# SCH_Final-2_2024-12-22.net
KiCad netlist of a schematic drawn in EasyEDA
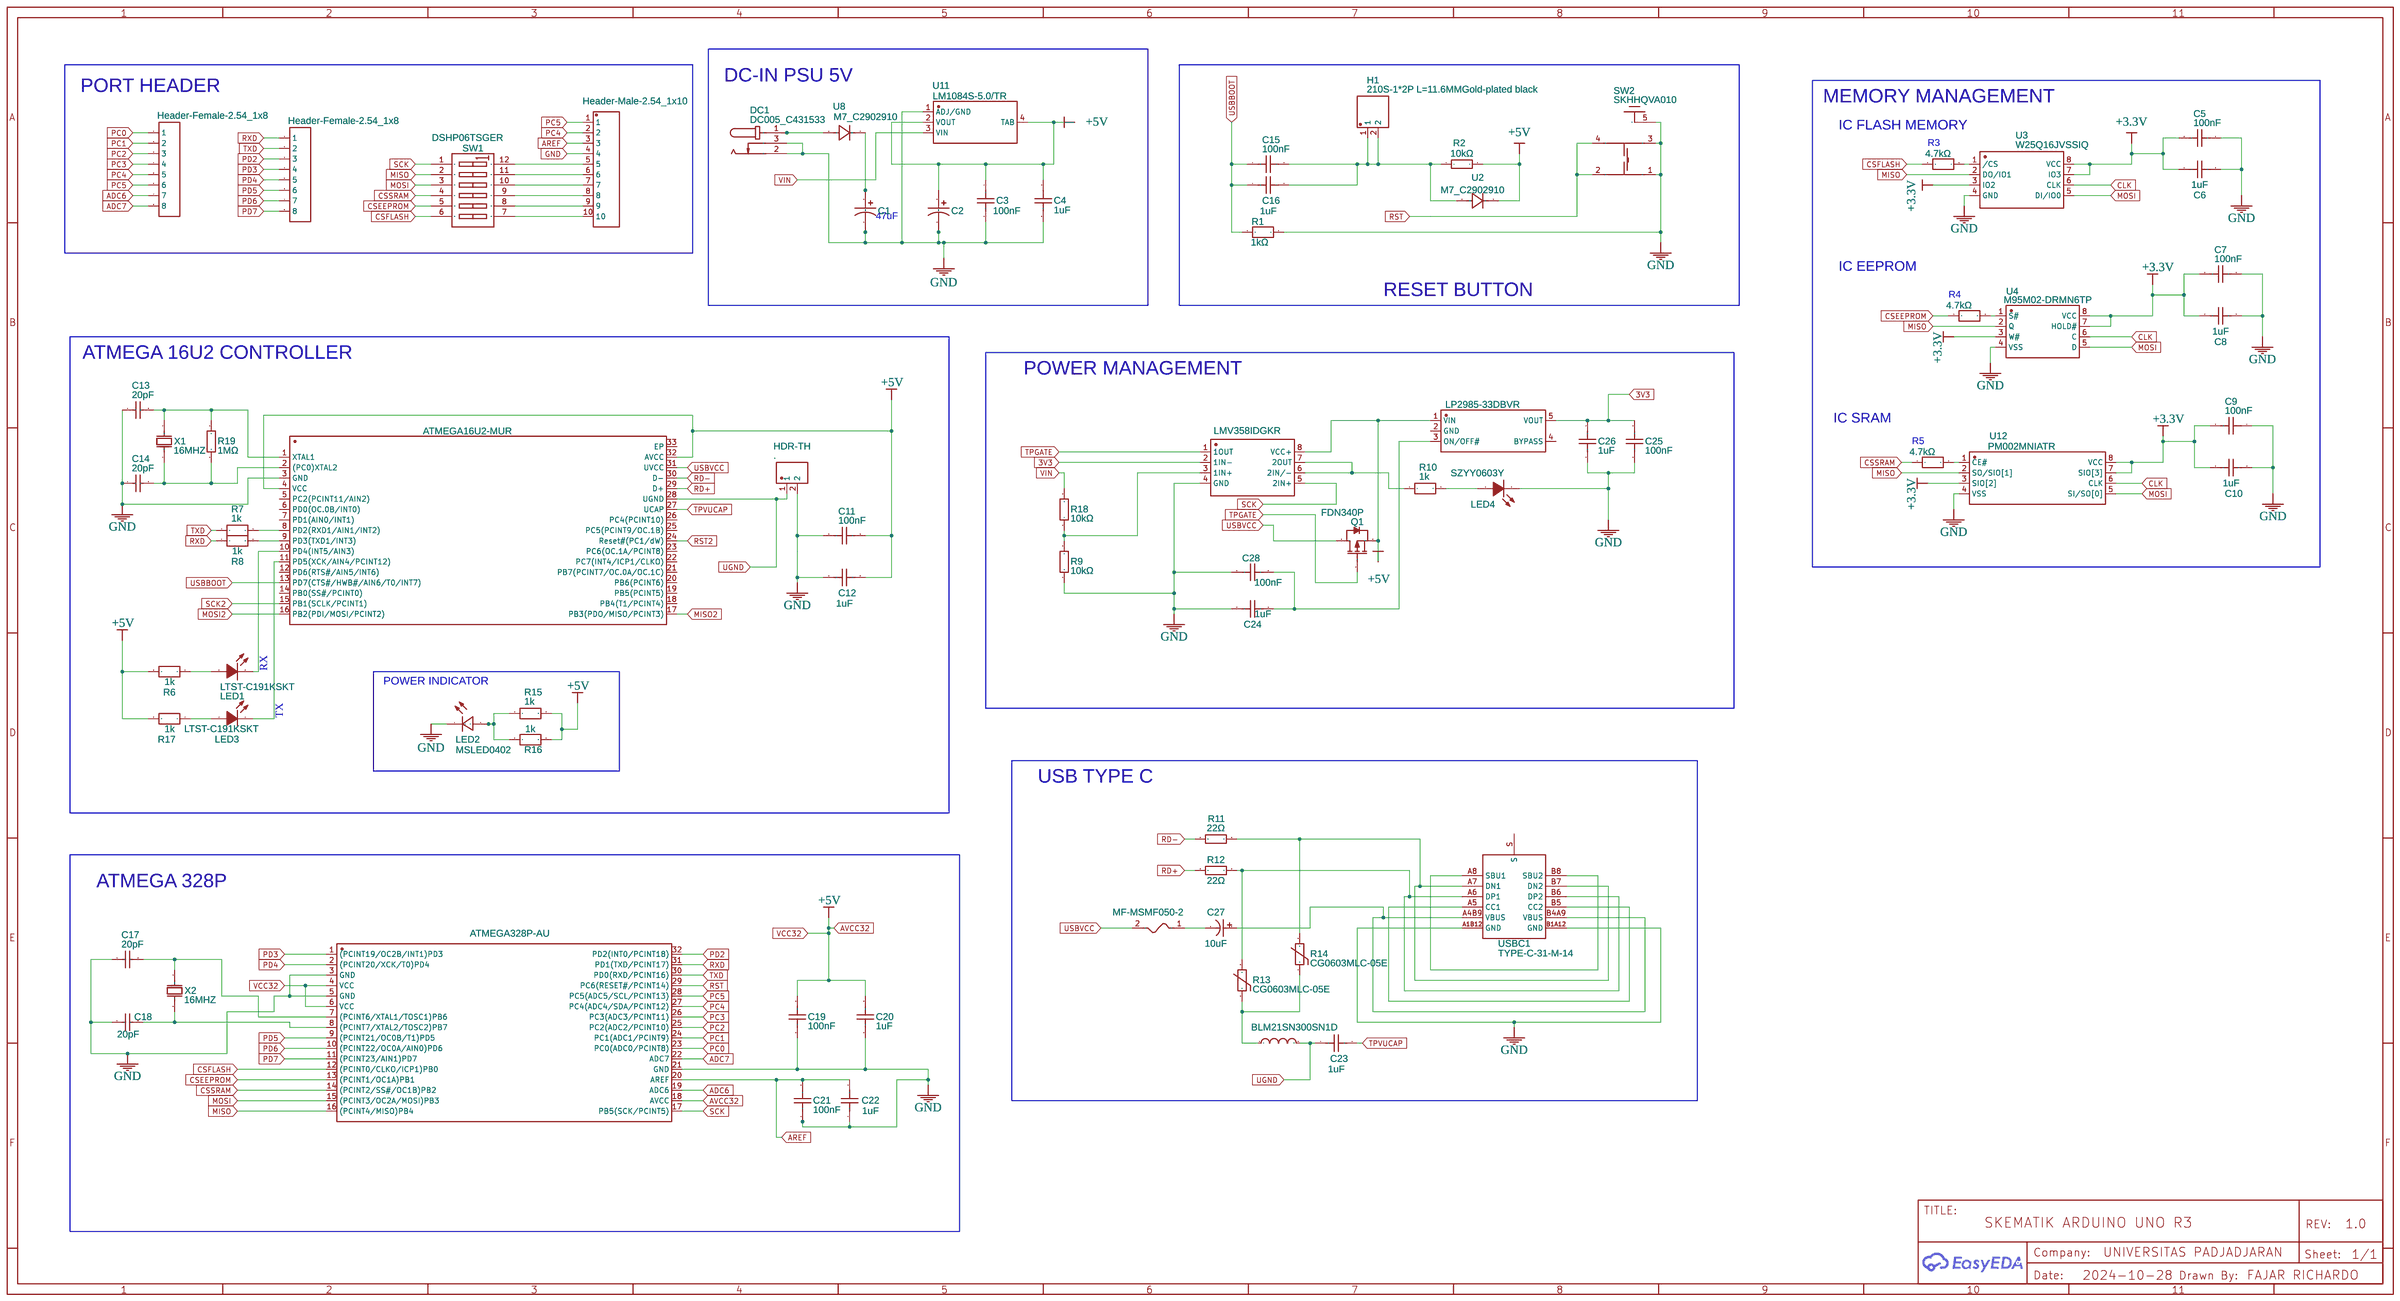
[diagram p0: schematic sheet]

(export (version "E")
  (design (tool "Eeschema 10.0.6"))
  (components
    (comp (ref "C1")
      (value "47uF")
      (fields
        (field (name "Manufacturer Part") "16SEV47M6.3X5.5")
        (field (name "Manufacturer") "rubycon(红宝石)")
      )
      (libsource (lib "") (part "16SEV47M6.3X5.5"))
    )
    (comp (ref "C2")
      (value "47uF")
      (fields
        (field (name "Manufacturer Part") "16SEV47M6.3X5.5")
        (field (name "Manufacturer") "rubycon(红宝石)")
      )
      (libsource (lib "") (part "16SEV47M6.3X5.5"))
    )
    (comp (ref "C3") (value "100nF") (libsource (lib "") (part "C_0402_US_1")))
    (comp (ref "C4") (value "1uF") (libsource (lib "") (part "C_0402_US_1")))
    (comp (ref "C5")
      (value "100nF")
      (fields
        (field (name "Manufacturer Part") "CL02A104KQ2NNNC")
        (field (name "Manufacturer") "SAMSUNG(三星)")
      )
      (libsource (lib "") (part "CL02A104KQ2NNNC"))
    )
    (comp (ref "C6")
      (value "1uF")
      (fields
        (field (name "Manufacturer Part") "1uf/250V/CBBCapacitor")
        (field (name "Manufacturer") "ReliaPro")
      )
      (libsource (lib "") (part "1uf/250V/CBBCapacitor"))
    )
    (comp (ref "C7")
      (value "100nF")
      (fields
        (field (name "Manufacturer Part") "CL02A104KQ2NNNC")
        (field (name "Manufacturer") "SAMSUNG(三星)")
      )
      (libsource (lib "") (part "CL02A104KQ2NNNC"))
    )
    (comp (ref "C8")
      (value "1uF")
      (fields
        (field (name "Manufacturer Part") "1uf/250V/CBBCapacitor")
        (field (name "Manufacturer") "ReliaPro")
      )
      (libsource (lib "") (part "1uf/250V/CBBCapacitor"))
    )
    (comp (ref "C9")
      (value "100nF")
      (fields
        (field (name "Manufacturer Part") "CL02A104KQ2NNNC")
        (field (name "Manufacturer") "SAMSUNG(三星)")
      )
      (libsource (lib "") (part "CL02A104KQ2NNNC"))
    )
    (comp (ref "C10")
      (value "1uF")
      (fields
        (field (name "Manufacturer Part") "1uf/250V/CBBCapacitor")
        (field (name "Manufacturer") "ReliaPro")
      )
      (libsource (lib "") (part "1uf/250V/CBBCapacitor"))
    )
    (comp (ref "C11") (value "100nF") (libsource (lib "") (part "C_0402_US")))
    (comp (ref "C12") (value "1uF") (libsource (lib "") (part "C_0402_US")))
    (comp (ref "C13")
      (value "20pF")
      (fields
        (field (name "Manufacturer Part") "GRM1885C1H200JA01D")
        (field (name "Manufacturer") "muRata(村田)")
      )
      (libsource (lib "") (part "GRM1885C1H200JA01D"))
    )
    (comp (ref "C14")
      (value "20pF")
      (fields
        (field (name "Manufacturer Part") "GRM1885C1H200JA01D")
        (field (name "Manufacturer") "muRata(村田)")
      )
      (libsource (lib "") (part "GRM1885C1H200JA01D"))
    )
    (comp (ref "C15") (value "100nF") (libsource (lib "") (part "C_0402_US")))
    (comp (ref "C16") (value "1uF") (libsource (lib "") (part "C_0402_US")))
    (comp (ref "C17")
      (value "20pF")
      (fields
        (field (name "Manufacturer Part") "GRM1885C1H200JA01D")
        (field (name "Manufacturer") "muRata(村田)")
      )
      (libsource (lib "") (part "GRM1885C1H200JA01D"))
    )
    (comp (ref "C18")
      (value "20pF")
      (fields
        (field (name "Manufacturer Part") "GRM1885C1H200JA01D")
        (field (name "Manufacturer") "muRata(村田)")
      )
      (libsource (lib "") (part "GRM1885C1H200JA01D"))
    )
    (comp (ref "C19") (value "100nF") (libsource (lib "") (part "C_0402_US_2")))
    (comp (ref "C20") (value "1uF") (libsource (lib "") (part "C_0402_US_2")))
    (comp (ref "C21") (value "100nF") (libsource (lib "") (part "C_0402_US_2")))
    (comp (ref "C22") (value "1uF") (libsource (lib "") (part "C_0402_US_2")))
    (comp (ref "C23") (value "1uF") (libsource (lib "") (part "C_0402_US")))
    (comp (ref "C24") (value "1uF") (libsource (lib "") (part "C_0402_US")))
    (comp (ref "C25") (value "100nF") (libsource (lib "") (part "C_0402_US_1")))
    (comp (ref "C26") (value "1uF") (libsource (lib "") (part "C_0402_US_1")))
    (comp (ref "C27")
      (value "10uF")
      (fields
        (field (name "Manufacturer Part") "KS106M050C07RR0VH2FP0")
        (field (name "Manufacturer") "CX(承兴)")
      )
      (libsource (lib "") (part "electrolytic capacitor10UF50V"))
    )
    (comp (ref "C28") (value "100nF") (libsource (lib "") (part "C_0402_US")))
    (comp (ref "DC1")
      (value "DC005_C431533")
      (fields (field (name "Manufacturer Part") "DC005") (field (name "Manufacturer") "SHOU HAN(首韩)"))
      (libsource (lib "") (part "DC005_C431533"))
    )
    (comp (ref "H1")
      (value "210S-1*2P L=11.6MMGold-plated black")
      (fields (field (name "Manufacturer Part") "B-2100S02P-A110") (field (name "Manufacturer") "Ckmtw(灿科盟)"))
      (libsource (lib "") (part "210S-1*2P L=11.6MMGold-plated black"))
    )
    (comp (ref "HDR-TH")
      (value ".")
      (fields (field (name "Manufacturer Part") "22-28-4020") (field (name "Manufacturer") "MOLEX"))
      (libsource (lib "") (part "22-28-4020"))
    )
    (comp (ref "LED1")
      (value "LTST-C191KSKT")
      (fields (field (name "Manufacturer") "LITEON(光宝)"))
      (libsource (lib "") (part "LTST-C191KSKT"))
    )
    (comp (ref "LED2") (value "MSLED0402") (libsource (lib "") (part "MSLED0402")))
    (comp (ref "LED3")
      (value "LTST-C191KSKT")
      (fields (field (name "Manufacturer") "LITEON(光宝)"))
      (libsource (lib "") (part "LTST-C191KSKT"))
    )
    (comp (ref "LED4")
      (value "SZYY0603Y")
      (fields (field (name "Manufacturer") "yongyu(永裕光电)"))
      (libsource (lib "") (part "SZYY0603Y"))
    )
    (comp (ref "PBX")
      (value "Header-Male-2.54_1x10")
      (fields (field (name "Manufacturer Part") "2.54-1*10P针") (field (name "Manufacturer") "BOOMELE(博穆精密)"))
      (libsource (lib "") (part "Header-Male-2.54_1x10"))
    )
    (comp (ref "PCX")
      (value "Header-Female-2.54_1x8")
      (fields (field (name "Manufacturer Part") "2.54-1*8P母环保") (field (name "Manufacturer") "BOOMELE(博穆精密)"))
      (libsource (lib "") (part "Header-Female-2.54_1x8_1"))
    )
    (comp (ref "PDX")
      (value "Header-Female-2.54_1x8")
      (fields (field (name "Manufacturer Part") "2.54-1*8P母环保") (field (name "Manufacturer") "BOOMELE(博穆精密)"))
      (libsource (lib "") (part "Header-Female-2.54_1x8"))
    )
    (comp (ref "Q1")
      (value "FDN340P")
      (fields (field (name "Manufacturer") "onsemi(安森美)"))
      (libsource (lib "") (part "FDN340P"))
    )
    (comp (ref "R1") (value "1kΩ") (libsource (lib "") (part "R_0402_EU")))
    (comp (ref "R2")
      (value "10kΩ")
      (fields (field (name "Manufacturer Part") "RC0603FR-0710KL") (field (name "Manufacturer") "YAGEO(国巨)"))
      (libsource (lib "") (part "RC0603FR-0710KL"))
    )
    (comp (ref "R6") (value "1k") (libsource (lib "") (part "R_0402_EU")))
    (comp (ref "R7") (value "1k") (libsource (lib "") (part "R_0402_EU_1")))
    (comp (ref "R8") (value "1k") (libsource (lib "") (part "R_0402_EU_1")))
    (comp (ref "R9")
      (value "10kΩ")
      (fields (field (name "Manufacturer Part") "RC0603FR-0710KL") (field (name "Manufacturer") "YAGEO(国巨)"))
      (libsource (lib "") (part "RC0603FR-0710KL_1"))
    )
    (comp (ref "R10") (value "1k") (libsource (lib "") (part "R_0402_EU_1")))
    (comp (ref "R11")
      (value "22Ω")
      (fields (field (name "Manufacturer Part") "RC0805FR-0722RL") (field (name "Manufacturer") "YAGEO(国巨)"))
      (libsource (lib "") (part "RC0805FR-0722RL"))
    )
    (comp (ref "R12")
      (value "22Ω")
      (fields (field (name "Manufacturer Part") "RC0805FR-0722RL") (field (name "Manufacturer") "YAGEO(国巨)"))
      (libsource (lib "") (part "RC0805FR-0722RL"))
    )
    (comp (ref "R13")
      (value "CG0603MLC-05E")
      (fields (field (name "Manufacturer") "BOURNS"))
      (libsource (lib "") (part "CG0603MLC-05E"))
    )
    (comp (ref "R14")
      (value "CG0603MLC-05E")
      (fields (field (name "Manufacturer") "BOURNS"))
      (libsource (lib "") (part "CG0603MLC-05E"))
    )
    (comp (ref "R15") (value "1k") (libsource (lib "") (part "R_0402_EU_1")))
    (comp (ref "R16") (value "1k") (libsource (lib "") (part "R_0402_EU_1")))
    (comp (ref "R17") (value "1k") (libsource (lib "") (part "R_0402_EU")))
    (comp (ref "R18")
      (value "10kΩ")
      (fields (field (name "Manufacturer Part") "RC0603FR-0710KL") (field (name "Manufacturer") "YAGEO(国巨)"))
      (libsource (lib "") (part "RC0603FR-0710KL_1"))
    )
    (comp (ref "R19")
      (value "1MΩ")
      (fields (field (name "Manufacturer Part") "RC0603FR-071ML") (field (name "Manufacturer") "YAGEO(国巨)"))
      (libsource (lib "") (part "RC0603FR-071ML"))
    )
    (comp (ref "SW1")
      (value "DSHP06TSGER")
      (fields (field (name "Manufacturer Part") "DSHP06TSGET") (field (name "Manufacturer") "YE"))
      (libsource (lib "") (part "DSHP06TSGER"))
    )
    (comp (ref "SW2")
      (value "SKHHQVA010")
      (fields (field (name "Manufacturer") "ALPSALPINE(阿尔卑斯阿尔派)"))
      (libsource (lib "") (part "SKHHQVA010"))
    )
    (comp (ref "U1")
      (value "ATMEGA16U2-MUR")
      (fields (field (name "Manufacturer") "MICROCHIP(美国微芯)"))
      (libsource (lib "") (part "ATMEGA16U2-MUR"))
    )
    (comp (ref "U2")
      (value "M7_C2902910")
      (fields (field (name "Manufacturer Part") "M7") (field (name "Manufacturer") "MSKSEMI(美森科)"))
      (libsource (lib "") (part "M7_C2902910"))
    )
    (comp (ref "U3")
      (value "W25Q16JVSSIQ")
      (fields (field (name "Manufacturer") "WINBOND(华邦)"))
      (libsource (lib "") (part "W25Q16JVSSIQ"))
    )
    (comp (ref "U4")
      (value "M95M02-DRMN6TP")
      (fields (field (name "Manufacturer") "ST(意法半导体)"))
      (libsource (lib "") (part "M95M02-DRMN6TP"))
    )
    (comp (ref "U5")
      (value "ATMEGA328P-AU")
      (fields (field (name "Manufacturer") "MICROCHIP(美国微芯)"))
      (libsource (lib "") (part "ATMEGA328P-AU"))
    )
    (comp (ref "U6")
      (value "BLM21SN300SN1D")
      (fields (field (name "Manufacturer") "muRata(村田)"))
      (libsource (lib "") (part "BLM21SN300SN1D"))
    )
    (comp (ref "U7")
      (value "MF-MSMF050-2")
      (fields (field (name "Manufacturer") "BOURNS"))
      (libsource (lib "") (part "MF-MSMF050-2"))
    )
    (comp (ref "U8")
      (value "M7_C2902910")
      (fields (field (name "Manufacturer Part") "M7") (field (name "Manufacturer") "MSKSEMI(美森科)"))
      (libsource (lib "") (part "M7_C2902910"))
    )
    (comp (ref "U9")
      (value "LP2985-33DBVR")
      (fields (field (name "Manufacturer") "TI(德州仪器)"))
      (libsource (lib "") (part "LP2985-33DBVR"))
    )
    (comp (ref "U10")
      (value "LMV358IDGKR")
      (fields (field (name "Manufacturer") "TI(德州仪器)"))
      (libsource (lib "") (part "LMV358IDGKR"))
    )
    (comp (ref "U11")
      (value "LM1084S-5.0/TR")
      (fields (field (name "Manufacturer") "HGSEMI(华冠)"))
      (libsource (lib "") (part "LM1084S-5.0/TR"))
    )
    (comp (ref "U12")
      (value "PM002MNIATR")
      (fields (field (name "Manufacturer") "Siproin(上海矽朋)"))
      (libsource (lib "") (part "PM002MNIATR"))
    )
    (comp (ref "U17")
      (value "4.7kΩ")
      (fields (field (name "Manufacturer Part") "0805 ±1% 4K7") (field (name "Manufacturer") "VO(翔胜)"))
      (libsource (lib "") (part "0805 ±1% 4K7"))
    )
    (comp (ref "U18")
      (value "4.7kΩ")
      (fields (field (name "Manufacturer Part") "0805 ±1% 4K7") (field (name "Manufacturer") "VO(翔胜)"))
      (libsource (lib "") (part "0805 ±1% 4K7"))
    )
    (comp (ref "U19")
      (value "4.7kΩ")
      (fields (field (name "Manufacturer Part") "0805 ±1% 4K7") (field (name "Manufacturer") "VO(翔胜)"))
      (libsource (lib "") (part "0805 ±1% 4K7"))
    )
    (comp (ref "USBC1")
      (value "TYPE-C-31-M-14")
      (fields (field (name "Manufacturer") "韩国韩荣"))
      (libsource (lib "") (part "TYPE-C-31-M-14"))
    )
    (comp (ref "X1")
      (value "16MHZ")
      (fields (field (name "Manufacturer Part") "X503216MSD2GC") (field (name "Manufacturer") "YXC"))
      (libsource (lib "") (part "X503216MSD2GC"))
    )
    (comp (ref "X2")
      (value "16MHZ")
      (fields (field (name "Manufacturer Part") "X503216MSD2GC") (field (name "Manufacturer") "YXC"))
      (libsource (lib "") (part "X503216MSD2GC"))
    )
  )
  (nets
    (net (code "1") (name "+3.3V") (class "Default")
      (node (ref "C10") (pin "1") (pinfunction "1_1") (pintype "unspecified"))
      (node (ref "C5") (pin "2") (pinfunction "2_2") (pintype "unspecified"))
      (node (ref "C6") (pin "1") (pinfunction "1_1") (pintype "unspecified"))
      (node (ref "C7") (pin "2") (pinfunction "2_2") (pintype "unspecified"))
      (node (ref "C8") (pin "1") (pinfunction "1_1") (pintype "unspecified"))
      (node (ref "C9") (pin "2") (pinfunction "2_2") (pintype "unspecified"))
      (node (ref "U12") (pin "3") (pinfunction "SIO[2]_3") (pintype "unspecified"))
      (node (ref "U12") (pin "7") (pinfunction "SIO[3]_7") (pintype "unspecified"))
      (node (ref "U12") (pin "8") (pinfunction "VCC_8") (pintype "unspecified"))
      (node (ref "U3") (pin "3") (pinfunction "IO2_3") (pintype "unspecified"))
      (node (ref "U3") (pin "7") (pinfunction "IO3_7") (pintype "unspecified"))
      (node (ref "U3") (pin "8") (pinfunction "VCC_8") (pintype "unspecified"))
      (node (ref "U4") (pin "3") (pinfunction "W#_3") (pintype "unspecified"))
      (node (ref "U4") (pin "7") (pinfunction "HOLD#_7") (pintype "unspecified"))
      (node (ref "U4") (pin "8") (pinfunction "VCC_8") (pintype "unspecified"))
    )
    (net (code "2") (name "3V3") (class "Default")
      (node (ref "C25") (pin "1") (pinfunction "1_1") (pintype "unspecified"))
      (node (ref "C26") (pin "1") (pinfunction "1_1") (pintype "unspecified"))
      (node (ref "U10") (pin "2") (pinfunction "1IN-_2") (pintype "unspecified"))
      (node (ref "U9") (pin "5") (pinfunction "VOUT_5") (pintype "unspecified"))
    )
    (net (code "3") (name "ADC6") (class "Default")
      (node (ref "PDX") (pin "7") (pinfunction "7_7") (pintype "input"))
      (node (ref "U5") (pin "19") (pinfunction "ADC6_19") (pintype "unspecified"))
    )
    (net (code "4") (name "ADC7") (class "Default")
      (node (ref "PDX") (pin "8") (pinfunction "8_8") (pintype "input"))
      (node (ref "U5") (pin "22") (pinfunction "ADC7_22") (pintype "unspecified"))
    )
    (net (code "5") (name "AREF") (class "Default")
      (node (ref "C21") (pin "2") (pinfunction "2_2") (pintype "unspecified"))
      (node (ref "C22") (pin "2") (pinfunction "2_2") (pintype "unspecified"))
      (node (ref "PBX") (pin "3") (pinfunction "3_3") (pintype "unspecified"))
      (node (ref "U5") (pin "20") (pinfunction "AREF_20") (pintype "unspecified"))
    )
    (net (code "6") (name "AVCC32") (class "Default")
      (node (ref "C11") (pin "2") (pinfunction "2_2") (pintype "unspecified"))
      (node (ref "C12") (pin "2") (pinfunction "2_2") (pintype "unspecified"))
      (node (ref "C19") (pin "2") (pinfunction "2_2") (pintype "unspecified"))
      (node (ref "C2") (pin "1") (pinfunction "1_1") (pintype "unspecified"))
      (node (ref "C20") (pin "2") (pinfunction "2_2") (pintype "unspecified"))
      (node (ref "C3") (pin "1") (pinfunction "1_1") (pintype "unspecified"))
      (node (ref "C4") (pin "1") (pinfunction "1_1") (pintype "unspecified"))
      (node (ref "Q1") (pin "2") (pinfunction "S_2") (pintype "unspecified"))
      (node (ref "R15") (pin "2") (pinfunction "2_2") (pintype "unspecified"))
      (node (ref "R16") (pin "2") (pinfunction "2_2") (pintype "unspecified"))
      (node (ref "R17") (pin "2") (pinfunction "2_2") (pintype "unspecified"))
      (node (ref "R2") (pin "2") (pinfunction "2_2") (pintype "input"))
      (node (ref "R6") (pin "2") (pinfunction "2_2") (pintype "unspecified"))
      (node (ref "U1") (pin "32") (pinfunction "AVCC_32") (pintype "unspecified"))
      (node (ref "U1") (pin "4") (pinfunction "VCC_4") (pintype "unspecified"))
      (node (ref "U10") (pin "8") (pinfunction "VCC+_8") (pintype "unspecified"))
      (node (ref "U11") (pin "2") (pinfunction "VOUT_2") (pintype "unspecified"))
      (node (ref "U11") (pin "4") (pinfunction "TAB_4") (pintype "unspecified"))
      (node (ref "U2") (pin "1") (pinfunction "Cathode_1") (pintype "unspecified"))
      (node (ref "U5") (pin "18") (pinfunction "AVCC_18") (pintype "unspecified"))
      (node (ref "U5") (pin "4") (pinfunction "VCC_4") (pintype "unspecified"))
      (node (ref "U5") (pin "6") (pinfunction "VCC_6") (pintype "unspecified"))
      (node (ref "U9") (pin "1") (pinfunction "VIN_1") (pintype "unspecified"))
    )
    (net (code "7") (name "CLK") (class "Default")
      (node (ref "U12") (pin "6") (pinfunction "CLK_6") (pintype "unspecified"))
      (node (ref "U3") (pin "6") (pinfunction "CLK_6") (pintype "unspecified"))
      (node (ref "U4") (pin "6") (pinfunction "C_6") (pintype "unspecified"))
    )
    (net (code "8") (name "CSEEPROM") (class "Default")
      (node (ref "SW1") (pin "5") (pinfunction "A5_5") (pintype "input"))
      (node (ref "U18") (pin "1") (pinfunction "1_1") (pintype "unspecified"))
      (node (ref "U5") (pin "13") (pinfunction "(PCINT1/OC1A)PB1_13") (pintype "unspecified"))
    )
    (net (code "9") (name "CSFLASH") (class "Default")
      (node (ref "SW1") (pin "6") (pinfunction "A6_6") (pintype "input"))
      (node (ref "U17") (pin "1") (pinfunction "1_1") (pintype "unspecified"))
      (node (ref "U5") (pin "12") (pinfunction "(PCINT0/CLKO/ICP1)PB0_12") (pintype "unspecified"))
    )
    (net (code "10") (name "CSSRAM") (class "Default")
      (node (ref "SW1") (pin "4") (pinfunction "A4_4") (pintype "input"))
      (node (ref "U19") (pin "1") (pinfunction "1_1") (pintype "unspecified"))
      (node (ref "U5") (pin "14") (pinfunction "(PCINT2/SS#/OC1B)PB2_14") (pintype "unspecified"))
    )
    (net (code "11") (name "GND") (class "Default")
      (node (ref "C1") (pin "2") (pinfunction "2_2") (pintype "unspecified"))
      (node (ref "C10") (pin "2") (pinfunction "2_2") (pintype "unspecified"))
      (node (ref "C11") (pin "1") (pinfunction "1_1") (pintype "unspecified"))
      (node (ref "C12") (pin "1") (pinfunction "1_1") (pintype "unspecified"))
      (node (ref "C13") (pin "1") (pinfunction "1_1") (pintype "input"))
      (node (ref "C14") (pin "1") (pinfunction "1_1") (pintype "input"))
      (node (ref "C17") (pin "1") (pinfunction "1_1") (pintype "input"))
      (node (ref "C18") (pin "1") (pinfunction "1_1") (pintype "input"))
      (node (ref "C19") (pin "1") (pinfunction "1_1") (pintype "unspecified"))
      (node (ref "C2") (pin "2") (pinfunction "2_2") (pintype "unspecified"))
      (node (ref "C20") (pin "1") (pinfunction "1_1") (pintype "unspecified"))
      (node (ref "C21") (pin "1") (pinfunction "1_1") (pintype "unspecified"))
      (node (ref "C22") (pin "1") (pinfunction "1_1") (pintype "unspecified"))
      (node (ref "C24") (pin "1") (pinfunction "1_1") (pintype "unspecified"))
      (node (ref "C25") (pin "2") (pinfunction "2_2") (pintype "unspecified"))
      (node (ref "C26") (pin "2") (pinfunction "2_2") (pintype "unspecified"))
      (node (ref "C28") (pin "1") (pinfunction "1_1") (pintype "unspecified"))
      (node (ref "C3") (pin "2") (pinfunction "2_2") (pintype "unspecified"))
      (node (ref "C4") (pin "2") (pinfunction "2_2") (pintype "unspecified"))
      (node (ref "C5") (pin "1") (pinfunction "1_1") (pintype "unspecified"))
      (node (ref "C6") (pin "2") (pinfunction "2_2") (pintype "unspecified"))
      (node (ref "C7") (pin "1") (pinfunction "1_1") (pintype "unspecified"))
      (node (ref "C8") (pin "2") (pinfunction "2_2") (pintype "unspecified"))
      (node (ref "C9") (pin "1") (pinfunction "1_1") (pintype "unspecified"))
      (node (ref "DC1") (pin "2") (pinfunction "2_2") (pintype "unspecified"))
      (node (ref "DC1") (pin "3") (pinfunction "3_3") (pintype "unspecified"))
      (node (ref "HDR-TH") (pin "2") (pinfunction "2_2") (pintype "unspecified"))
      (node (ref "LED2") (pin "1") (pinfunction "C_1") (pintype "unspecified"))
      (node (ref "LED4") (pin "2") (pinfunction "-_2") (pintype "unspecified"))
      (node (ref "PBX") (pin "4") (pinfunction "4_4") (pintype "unspecified"))
      (node (ref "R1") (pin "1") (pinfunction "1_1") (pintype "unspecified"))
      (node (ref "R9") (pin "1") (pinfunction "1_1") (pintype "input"))
      (node (ref "SW2") (pin "1") (pinfunction "1_1") (pintype "unspecified"))
      (node (ref "SW2") (pin "3") (pinfunction "3_3") (pintype "unspecified"))
      (node (ref "SW2") (pin "5") (pinfunction "5_5") (pintype "unspecified"))
      (node (ref "U1") (pin "3") (pinfunction "GND_3") (pintype "unspecified"))
      (node (ref "U10") (pin "4") (pinfunction "GND_4") (pintype "unspecified"))
      (node (ref "U11") (pin "1") (pinfunction "ADJ/GND_1") (pintype "unspecified"))
      (node (ref "U12") (pin "4") (pinfunction "VSS_4") (pintype "unspecified"))
      (node (ref "U3") (pin "4") (pinfunction "GND_4") (pintype "unspecified"))
      (node (ref "U4") (pin "4") (pinfunction "VSS_4") (pintype "unspecified"))
      (node (ref "U5") (pin "21") (pinfunction "GND_21") (pintype "unspecified"))
      (node (ref "U5") (pin "3") (pinfunction "GND_3") (pintype "unspecified"))
      (node (ref "U5") (pin "5") (pinfunction "GND_5") (pintype "unspecified"))
      (node (ref "USBC1") (pin "A1B12") (pinfunction "GND_A1B12") (pintype "unspecified"))
      (node (ref "USBC1") (pin "B1A12") (pinfunction "GND_B1A12") (pintype "unspecified"))
    )
    (net (code "12") (name "MISO") (class "Default")
      (node (ref "SW1") (pin "2") (pinfunction "A2_2") (pintype "input"))
      (node (ref "U12") (pin "2") (pinfunction "SO/SIO[1]_2") (pintype "unspecified"))
      (node (ref "U3") (pin "2") (pinfunction "DO/IO1_2") (pintype "unspecified"))
      (node (ref "U4") (pin "2") (pinfunction "Q_2") (pintype "unspecified"))
      (node (ref "U5") (pin "16") (pinfunction "(PCINT4/MISO)PB4_16") (pintype "unspecified"))
    )
    (net (code "13") (name "MISO2") (class "Default")
      (node (ref "U1") (pin "17") (pinfunction "PB3(PDO/MISO/PCINT3)_17") (pintype "unspecified"))
    )
    (net (code "14") (name "MOSI") (class "Default")
      (node (ref "SW1") (pin "3") (pinfunction "A3_3") (pintype "input"))
      (node (ref "U12") (pin "5") (pinfunction "SI/SO[0]_5") (pintype "unspecified"))
      (node (ref "U3") (pin "5") (pinfunction "DI/IO0_5") (pintype "unspecified"))
      (node (ref "U4") (pin "5") (pinfunction "D_5") (pintype "unspecified"))
      (node (ref "U5") (pin "15") (pinfunction "(PCINT3/OC2A/MOSI)PB3_15") (pintype "unspecified"))
    )
    (net (code "15") (name "MOSI2") (class "Default")
      (node (ref "U1") (pin "16") (pinfunction "PB2(PDI/MOSI/PCINT2)_16") (pintype "unspecified"))
    )
    (net (code "16") (name "Net-(C27-+)") (class "Default")
      (node (ref "C27") (pin "1") (pinfunction "+_1") (pintype "input"))
      (node (ref "USBC1") (pin "A4B9") (pinfunction "VBUS_A4B9") (pintype "unspecified"))
      (node (ref "USBC1") (pin "B4A9") (pinfunction "VBUS_B4A9") (pintype "unspecified"))
    )
    (net (code "17") (name "Net-(C27--)") (class "Default")
      (node (ref "C27") (pin "2") (pinfunction "-_2") (pintype "input"))
      (node (ref "U7") (pin "1") (pinfunction "1_1") (pintype "unspecified"))
    )
    (net (code "18") (name "Net-(LED1-+)") (class "Default")
      (node (ref "LED1") (pin "2") (pinfunction "+_2") (pintype "unspecified"))
      (node (ref "R6") (pin "1") (pinfunction "1_1") (pintype "unspecified"))
    )
    (net (code "19") (name "Net-(LED1--)") (class "Default")
      (node (ref "LED1") (pin "1") (pinfunction "-_1") (pintype "unspecified"))
      (node (ref "U1") (pin "10") (pinfunction "PD4(INT5/AIN3)_10") (pintype "unspecified"))
    )
    (net (code "20") (name "Net-(LED2-A)") (class "Default")
      (node (ref "LED2") (pin "2") (pinfunction "A_2") (pintype "unspecified"))
      (node (ref "R15") (pin "1") (pinfunction "1_1") (pintype "unspecified"))
      (node (ref "R16") (pin "1") (pinfunction "1_1") (pintype "unspecified"))
    )
    (net (code "21") (name "Net-(LED3-+)") (class "Default")
      (node (ref "LED3") (pin "2") (pinfunction "+_2") (pintype "unspecified"))
      (node (ref "R17") (pin "1") (pinfunction "1_1") (pintype "unspecified"))
    )
    (net (code "22") (name "Net-(LED3--)") (class "Default")
      (node (ref "LED3") (pin "1") (pinfunction "-_1") (pintype "unspecified"))
      (node (ref "U1") (pin "11") (pinfunction "PD5(XCK/AIN4/PCINT12)_11") (pintype "unspecified"))
    )
    (net (code "23") (name "Net-(LED4-+)") (class "Default")
      (node (ref "LED4") (pin "1") (pinfunction "+_1") (pintype "unspecified"))
      (node (ref "R10") (pin "2") (pinfunction "2_2") (pintype "unspecified"))
    )
    (net (code "24") (name "Net-(R13-Pad1)") (class "Default")
      (node (ref "R13") (pin "1") (pinfunction "1_1") (pintype "unspecified"))
      (node (ref "R14") (pin "1") (pinfunction "1_1") (pintype "unspecified"))
      (node (ref "U6") (pin "1") (pinfunction "1_1") (pintype "unspecified"))
    )
    (net (code "25") (name "Net-(SW1-B1)") (class "Default")
      (node (ref "PBX") (pin "5") (pinfunction "5_5") (pintype "unspecified"))
      (node (ref "SW1") (pin "12") (pinfunction "B1_12") (pintype "input"))
    )
    (net (code "26") (name "Net-(SW1-B2)") (class "Default")
      (node (ref "PBX") (pin "6") (pinfunction "6_6") (pintype "unspecified"))
      (node (ref "SW1") (pin "11") (pinfunction "B2_11") (pintype "input"))
    )
    (net (code "27") (name "Net-(SW1-B3)") (class "Default")
      (node (ref "PBX") (pin "7") (pinfunction "7_7") (pintype "unspecified"))
      (node (ref "SW1") (pin "10") (pinfunction "B3_10") (pintype "input"))
    )
    (net (code "28") (name "Net-(SW1-B4)") (class "Default")
      (node (ref "PBX") (pin "8") (pinfunction "8_8") (pintype "unspecified"))
      (node (ref "SW1") (pin "9") (pinfunction "B4_9") (pintype "input"))
    )
    (net (code "29") (name "Net-(SW1-B5)") (class "Default")
      (node (ref "PBX") (pin "9") (pinfunction "9_9") (pintype "unspecified"))
      (node (ref "SW1") (pin "8") (pinfunction "B5_8") (pintype "input"))
    )
    (net (code "30") (name "Net-(SW1-B6)") (class "Default")
      (node (ref "PBX") (pin "10") (pinfunction "10_10") (pintype "unspecified"))
      (node (ref "SW1") (pin "7") (pinfunction "B6_7") (pintype "input"))
    )
    (net (code "31") (name "Net-(U1-(PC0)XTAL2)") (class "Default")
      (node (ref "C14") (pin "2") (pinfunction "2_2") (pintype "input"))
      (node (ref "R19") (pin "2") (pinfunction "2_2") (pintype "input"))
      (node (ref "U1") (pin "2") (pinfunction "(PC0)XTAL2_2") (pintype "unspecified"))
      (node (ref "X1") (pin "2") (pinfunction "OSC2_2") (pintype "input"))
    )
    (net (code "32") (name "Net-(U1-PD2(RXD1{slash}AIN1{slash}INT2))") (class "Default")
      (node (ref "R7") (pin "2") (pinfunction "2_2") (pintype "unspecified"))
      (node (ref "U1") (pin "8") (pinfunction "PD2(RXD1/AIN1/INT2)_8") (pintype "unspecified"))
    )
    (net (code "33") (name "Net-(U1-PD3(TXD1{slash}INT3))") (class "Default")
      (node (ref "R8") (pin "2") (pinfunction "2_2") (pintype "unspecified"))
      (node (ref "U1") (pin "9") (pinfunction "PD3(TXD1/INT3)_9") (pintype "unspecified"))
    )
    (net (code "34") (name "Net-(U1-XTAL1)") (class "Default")
      (node (ref "C13") (pin "2") (pinfunction "2_2") (pintype "input"))
      (node (ref "R19") (pin "1") (pinfunction "1_1") (pintype "input"))
      (node (ref "U1") (pin "1") (pinfunction "XTAL1_1") (pintype "unspecified"))
      (node (ref "X1") (pin "1") (pinfunction "OSC1_1") (pintype "input"))
    )
    (net (code "35") (name "Net-(U2-Anode)") (class "Default")
      (node (ref "C15") (pin "2") (pinfunction "2_2") (pintype "unspecified"))
      (node (ref "C16") (pin "2") (pinfunction "2_2") (pintype "unspecified"))
      (node (ref "H1") (pin "1") (pinfunction "1_1") (pintype "unspecified"))
      (node (ref "H1") (pin "2") (pinfunction "2_2") (pintype "unspecified"))
      (node (ref "R2") (pin "1") (pinfunction "1_1") (pintype "input"))
      (node (ref "U2") (pin "2") (pinfunction "Anode_2") (pintype "unspecified"))
    )
    (net (code "36") (name "Net-(U3-{slash}CS)") (class "Default")
      (node (ref "U17") (pin "2") (pinfunction "2_2") (pintype "unspecified"))
      (node (ref "U3") (pin "1") (pinfunction "/CS_1") (pintype "unspecified"))
    )
    (net (code "37") (name "Net-(U4-S#)") (class "Default")
      (node (ref "U18") (pin "2") (pinfunction "2_2") (pintype "unspecified"))
      (node (ref "U4") (pin "1") (pinfunction "S#_1") (pintype "unspecified"))
    )
    (net (code "38") (name "Net-(U5-(PCINT6{slash}XTAL1{slash}TOSC1)PB6)") (class "Default")
      (node (ref "C17") (pin "2") (pinfunction "2_2") (pintype "input"))
      (node (ref "U5") (pin "7") (pinfunction "(PCINT6/XTAL1/TOSC1)PB6_7") (pintype "unspecified"))
      (node (ref "X2") (pin "1") (pinfunction "OSC1_1") (pintype "input"))
    )
    (net (code "39") (name "Net-(U5-(PCINT7{slash}XTAL2{slash}TOSC2)PB7)") (class "Default")
      (node (ref "C18") (pin "2") (pinfunction "2_2") (pintype "input"))
      (node (ref "U5") (pin "8") (pinfunction "(PCINT7/XTAL2/TOSC2)PB7_8") (pintype "unspecified"))
      (node (ref "X2") (pin "2") (pinfunction "OSC2_2") (pintype "input"))
    )
    (net (code "40") (name "Net-(U8-Anode)") (class "Default")
      (node (ref "DC1") (pin "1") (pinfunction "1_1") (pintype "unspecified"))
      (node (ref "U8") (pin "2") (pinfunction "Anode_2") (pintype "unspecified"))
    )
    (net (code "41") (name "Net-(U8-Cathode)") (class "Default")
      (node (ref "C1") (pin "1") (pinfunction "1_1") (pintype "unspecified"))
      (node (ref "U8") (pin "1") (pinfunction "Cathode_1") (pintype "unspecified"))
    )
    (net (code "42") (name "Net-(U9-ON{slash}OFF#)") (class "Default")
      (node (ref "C24") (pin "2") (pinfunction "2_2") (pintype "unspecified"))
      (node (ref "C28") (pin "2") (pinfunction "2_2") (pintype "unspecified"))
      (node (ref "U9") (pin "3") (pinfunction "ON/OFF#_3") (pintype "unspecified"))
    )
    (net (code "43") (name "Net-(U10-1IN+)") (class "Default")
      (node (ref "R18") (pin "1") (pinfunction "1_1") (pintype "input"))
      (node (ref "R9") (pin "2") (pinfunction "2_2") (pintype "input"))
      (node (ref "U10") (pin "3") (pinfunction "1IN+_3") (pintype "unspecified"))
    )
    (net (code "44") (name "Net-(U10-2IN{slash}-)") (class "Default")
      (node (ref "R10") (pin "1") (pinfunction "1_1") (pintype "unspecified"))
      (node (ref "U10") (pin "6") (pinfunction "2IN/-_6") (pintype "unspecified"))
      (node (ref "U10") (pin "7") (pinfunction "2OUT_7") (pintype "unspecified"))
    )
    (net (code "45") (name "Net-(U12-CE#)") (class "Default")
      (node (ref "U12") (pin "1") (pinfunction "CE#_1") (pintype "unspecified"))
      (node (ref "U19") (pin "2") (pinfunction "2_2") (pintype "unspecified"))
    )
    (net (code "46") (name "Net-(USBC1-CC1)") (class "Default")
      (node (ref "USBC1") (pin "A5") (pinfunction "CC1_A5") (pintype "unspecified"))
      (node (ref "USBC1") (pin "B5") (pinfunction "CC2_B5") (pintype "unspecified"))
    )
    (net (code "47") (name "Net-(USBC1-DN1)") (class "Default")
      (node (ref "R11") (pin "1") (pinfunction "1_1") (pintype "unspecified"))
      (node (ref "R14") (pin "2") (pinfunction "2_2") (pintype "unspecified"))
      (node (ref "USBC1") (pin "A7") (pinfunction "DN1_A7") (pintype "unspecified"))
      (node (ref "USBC1") (pin "B7") (pinfunction "DN2_B7") (pintype "unspecified"))
    )
    (net (code "48") (name "Net-(USBC1-DP1)") (class "Default")
      (node (ref "R12") (pin "1") (pinfunction "1_1") (pintype "unspecified"))
      (node (ref "R13") (pin "2") (pinfunction "2_2") (pintype "unspecified"))
      (node (ref "USBC1") (pin "A6") (pinfunction "DP1_A6") (pintype "unspecified"))
      (node (ref "USBC1") (pin "B6") (pinfunction "DP2_B6") (pintype "unspecified"))
    )
    (net (code "49") (name "Net-(USBC1-SBU1)") (class "Default")
      (node (ref "USBC1") (pin "A8") (pinfunction "SBU1_A8") (pintype "unspecified"))
      (node (ref "USBC1") (pin "B8") (pinfunction "SBU2_B8") (pintype "unspecified"))
    )
    (net (code "50") (name "PC0") (class "Default")
      (node (ref "PDX") (pin "1") (pinfunction "1_1") (pintype "input"))
      (node (ref "U5") (pin "23") (pinfunction "PC0(ADC0/PCINT8)_23") (pintype "unspecified"))
    )
    (net (code "51") (name "PC1") (class "Default")
      (node (ref "PDX") (pin "2") (pinfunction "2_2") (pintype "input"))
      (node (ref "U5") (pin "24") (pinfunction "PC1(ADC1/PCINT9)_24") (pintype "unspecified"))
    )
    (net (code "52") (name "PC2") (class "Default")
      (node (ref "PDX") (pin "3") (pinfunction "3_3") (pintype "input"))
      (node (ref "U5") (pin "25") (pinfunction "PC2(ADC2/PCINT10)_25") (pintype "unspecified"))
    )
    (net (code "53") (name "PC3") (class "Default")
      (node (ref "PDX") (pin "4") (pinfunction "4_4") (pintype "input"))
      (node (ref "U5") (pin "26") (pinfunction "PC3(ADC3/PCINT11)_26") (pintype "unspecified"))
    )
    (net (code "54") (name "PC4") (class "Default")
      (node (ref "PBX") (pin "2") (pinfunction "2_2") (pintype "unspecified"))
      (node (ref "PDX") (pin "5") (pinfunction "5_5") (pintype "input"))
      (node (ref "U5") (pin "27") (pinfunction "PC4(ADC4/SDA/PCINT12)_27") (pintype "unspecified"))
    )
    (net (code "55") (name "PC5") (class "Default")
      (node (ref "PBX") (pin "1") (pinfunction "1_1") (pintype "unspecified"))
      (node (ref "PDX") (pin "6") (pinfunction "6_6") (pintype "input"))
      (node (ref "U5") (pin "28") (pinfunction "PC5(ADC5/SCL/PCINT13)_28") (pintype "unspecified"))
    )
    (net (code "56") (name "PD2") (class "Default")
      (node (ref "PCX") (pin "3") (pinfunction "3_3") (pintype "input"))
      (node (ref "U5") (pin "32") (pinfunction "PD2(INT0/PCINT18)_32") (pintype "unspecified"))
    )
    (net (code "57") (name "PD3") (class "Default")
      (node (ref "PCX") (pin "4") (pinfunction "4_4") (pintype "input"))
      (node (ref "U5") (pin "1") (pinfunction "(PCINT19/OC2B/INT1)PD3_1") (pintype "unspecified"))
    )
    (net (code "58") (name "PD4") (class "Default")
      (node (ref "PCX") (pin "5") (pinfunction "5_5") (pintype "input"))
      (node (ref "U5") (pin "2") (pinfunction "(PCINT20/XCK/T0)PD4_2") (pintype "unspecified"))
    )
    (net (code "59") (name "PD5") (class "Default")
      (node (ref "PCX") (pin "6") (pinfunction "6_6") (pintype "input"))
      (node (ref "U5") (pin "9") (pinfunction "(PCINT21/OC0B/T1)PD5_9") (pintype "unspecified"))
    )
    (net (code "60") (name "PD6") (class "Default")
      (node (ref "PCX") (pin "7") (pinfunction "7_7") (pintype "input"))
      (node (ref "U5") (pin "10") (pinfunction "(PCINT22/OC0A/AIN0)PD6_10") (pintype "unspecified"))
    )
    (net (code "61") (name "PD7") (class "Default")
      (node (ref "PCX") (pin "8") (pinfunction "8_8") (pintype "input"))
      (node (ref "U5") (pin "11") (pinfunction "(PCINT23/AIN1)PD7_11") (pintype "unspecified"))
    )
    (net (code "62") (name "RD+") (class "Default")
      (node (ref "R12") (pin "2") (pinfunction "2_2") (pintype "unspecified"))
      (node (ref "U1") (pin "29") (pinfunction "D+_29") (pintype "unspecified"))
    )
    (net (code "63") (name "RD-") (class "Default")
      (node (ref "R11") (pin "2") (pinfunction "2_2") (pintype "unspecified"))
      (node (ref "U1") (pin "30") (pinfunction "D-_30") (pintype "unspecified"))
    )
    (net (code "64") (name "RST") (class "Default")
      (node (ref "SW2") (pin "2") (pinfunction "2_2") (pintype "unspecified"))
      (node (ref "SW2") (pin "4") (pinfunction "4_4") (pintype "unspecified"))
      (node (ref "U5") (pin "29") (pinfunction "PC6(RESET#/PCINT14)_29") (pintype "unspecified"))
    )
    (net (code "65") (name "RST2") (class "Default")
      (node (ref "U1") (pin "24") (pinfunction "Reset#(PC1/dW)_24") (pintype "unspecified"))
    )
    (net (code "66") (name "RXD") (class "Default")
      (node (ref "PCX") (pin "1") (pinfunction "1_1") (pintype "input"))
      (node (ref "R8") (pin "1") (pinfunction "1_1") (pintype "unspecified"))
      (node (ref "U5") (pin "31") (pinfunction "PD1(TXD/PCINT17)_31") (pintype "unspecified"))
    )
    (net (code "67") (name "SCK") (class "Default")
      (node (ref "SW1") (pin "1") (pinfunction "A1_1") (pintype "input"))
      (node (ref "U10") (pin "5") (pinfunction "2IN+_5") (pintype "unspecified"))
      (node (ref "U5") (pin "17") (pinfunction "PB5(SCK/PCINT5)_17") (pintype "unspecified"))
    )
    (net (code "68") (name "SCK2") (class "Default")
      (node (ref "U1") (pin "15") (pinfunction "PB1(SCLK/PCINT1)_15") (pintype "unspecified"))
    )
    (net (code "69") (name "TPGATE") (class "Default")
      (node (ref "Q1") (pin "1") (pinfunction "G_1") (pintype "unspecified"))
      (node (ref "U10") (pin "1") (pinfunction "1OUT_1") (pintype "unspecified"))
    )
    (net (code "70") (name "TPVUCAP") (class "Default")
      (node (ref "C23") (pin "2") (pinfunction "2_2") (pintype "unspecified"))
      (node (ref "U1") (pin "27") (pinfunction "UCAP_27") (pintype "unspecified"))
    )
    (net (code "71") (name "TXD") (class "Default")
      (node (ref "PCX") (pin "2") (pinfunction "2_2") (pintype "input"))
      (node (ref "R7") (pin "1") (pinfunction "1_1") (pintype "unspecified"))
      (node (ref "U5") (pin "30") (pinfunction "PD0(RXD/PCINT16)_30") (pintype "unspecified"))
    )
    (net (code "72") (name "UGND") (class "Default")
      (node (ref "C23") (pin "1") (pinfunction "1_1") (pintype "unspecified"))
      (node (ref "HDR-TH") (pin "1") (pinfunction "1_1") (pintype "unspecified"))
      (node (ref "U1") (pin "28") (pinfunction "UGND_28") (pintype "unspecified"))
      (node (ref "U6") (pin "2") (pinfunction "2_2") (pintype "unspecified"))
    )
    (net (code "73") (name "USBBOOT") (class "Default")
      (node (ref "C15") (pin "1") (pinfunction "1_1") (pintype "unspecified"))
      (node (ref "C16") (pin "1") (pinfunction "1_1") (pintype "unspecified"))
      (node (ref "R1") (pin "2") (pinfunction "2_2") (pintype "unspecified"))
      (node (ref "U1") (pin "13") (pinfunction "PD7(CTS#/HWB#/AIN6/T0/INT7)_13") (pintype "unspecified"))
    )
    (net (code "74") (name "USBVCC") (class "Default")
      (node (ref "Q1") (pin "3") (pinfunction "D_3") (pintype "unspecified"))
      (node (ref "U1") (pin "31") (pinfunction "UVCC_31") (pintype "unspecified"))
      (node (ref "U7") (pin "2") (pinfunction "2_2") (pintype "unspecified"))
    )
    (net (code "75") (name "VIN") (class "Default")
      (node (ref "R18") (pin "2") (pinfunction "2_2") (pintype "input"))
      (node (ref "U11") (pin "3") (pinfunction "VIN_3") (pintype "unspecified"))
    )
    (net (code "76") (name "unconnected-(U1-EP-Pad33)") (class "Default")
      (node (ref "U1") (pin "33") (pinfunction "EP_33") (pintype "unspecified"))
    )
    (net (code "77") (name "unconnected-(U1-PB0(SS#{slash}PCINT0)-Pad14)") (class "Default")
      (node (ref "U1") (pin "14") (pinfunction "PB0(SS#/PCINT0)_14") (pintype "unspecified"))
    )
    (net (code "78") (name "unconnected-(U1-PB4(T1{slash}PCINT4)-Pad18)") (class "Default")
      (node (ref "U1") (pin "18") (pinfunction "PB4(T1/PCINT4)_18") (pintype "unspecified"))
    )
    (net (code "79") (name "unconnected-(U1-PB5(PCINT5)-Pad19)") (class "Default")
      (node (ref "U1") (pin "19") (pinfunction "PB5(PCINT5)_19") (pintype "unspecified"))
    )
    (net (code "80") (name "unconnected-(U1-PB6(PCINT6)-Pad20)") (class "Default")
      (node (ref "U1") (pin "20") (pinfunction "PB6(PCINT6)_20") (pintype "unspecified"))
    )
    (net (code "81") (name "unconnected-(U1-PB7(PCINT7{slash}OC.0A{slash}OC.1C)-Pad21)") (class "Default")
      (node (ref "U1") (pin "21") (pinfunction "PB7(PCINT7/OC.0A/OC.1C)_21") (pintype "unspecified"))
    )
    (net (code "82") (name "unconnected-(U1-PC2(PCINT11{slash}AIN2)-Pad5)") (class "Default")
      (node (ref "U1") (pin "5") (pinfunction "PC2(PCINT11/AIN2)_5") (pintype "unspecified"))
    )
    (net (code "83") (name "unconnected-(U1-PC4(PCINT10)-Pad26)") (class "Default")
      (node (ref "U1") (pin "26") (pinfunction "PC4(PCINT10)_26") (pintype "unspecified"))
    )
    (net (code "84") (name "unconnected-(U1-PC5(PCINT9{slash}OC.1B)-Pad25)") (class "Default")
      (node (ref "U1") (pin "25") (pinfunction "PC5(PCINT9/OC.1B)_25") (pintype "unspecified"))
    )
    (net (code "85") (name "unconnected-(U1-PC6(OC.1A{slash}PCINT8)-Pad23)") (class "Default")
      (node (ref "U1") (pin "23") (pinfunction "PC6(OC.1A/PCINT8)_23") (pintype "unspecified"))
    )
    (net (code "86") (name "unconnected-(U1-PC7(INT4{slash}ICP1{slash}CLKO)-Pad22)") (class "Default")
      (node (ref "U1") (pin "22") (pinfunction "PC7(INT4/ICP1/CLKO)_22") (pintype "unspecified"))
    )
    (net (code "87") (name "unconnected-(U1-PD0(OC.0B{slash}INT0)-Pad6)") (class "Default")
      (node (ref "U1") (pin "6") (pinfunction "PD0(OC.0B/INT0)_6") (pintype "unspecified"))
    )
    (net (code "88") (name "unconnected-(U1-PD1(AIN0{slash}INT1)-Pad7)") (class "Default")
      (node (ref "U1") (pin "7") (pinfunction "PD1(AIN0/INT1)_7") (pintype "unspecified"))
    )
    (net (code "89") (name "unconnected-(U1-PD6(RTS#{slash}AIN5{slash}INT6)-Pad12)") (class "Default")
      (node (ref "U1") (pin "12") (pinfunction "PD6(RTS#/AIN5/INT6)_12") (pintype "unspecified"))
    )
    (net (code "90") (name "unconnected-(U9-BYPASS-Pad4)") (class "Default")
      (node (ref "U9") (pin "4") (pinfunction "BYPASS_4") (pintype "unspecified"))
    )
    (net (code "91") (name "unconnected-(U9-GND-Pad2)") (class "Default")
      (node (ref "U9") (pin "2") (pinfunction "GND_2") (pintype "unspecified"))
    )
    (net (code "92") (name "unconnected-(USBC1-PadS)") (class "Default")
      (node (ref "USBC1") (pin "S") (pinfunction "S_S") (pintype "unspecified"))
    )
  )
)
